# 1-Schematic_MOBO_V3.net
KiCad netlist of a schematic drawn in EasyEDA
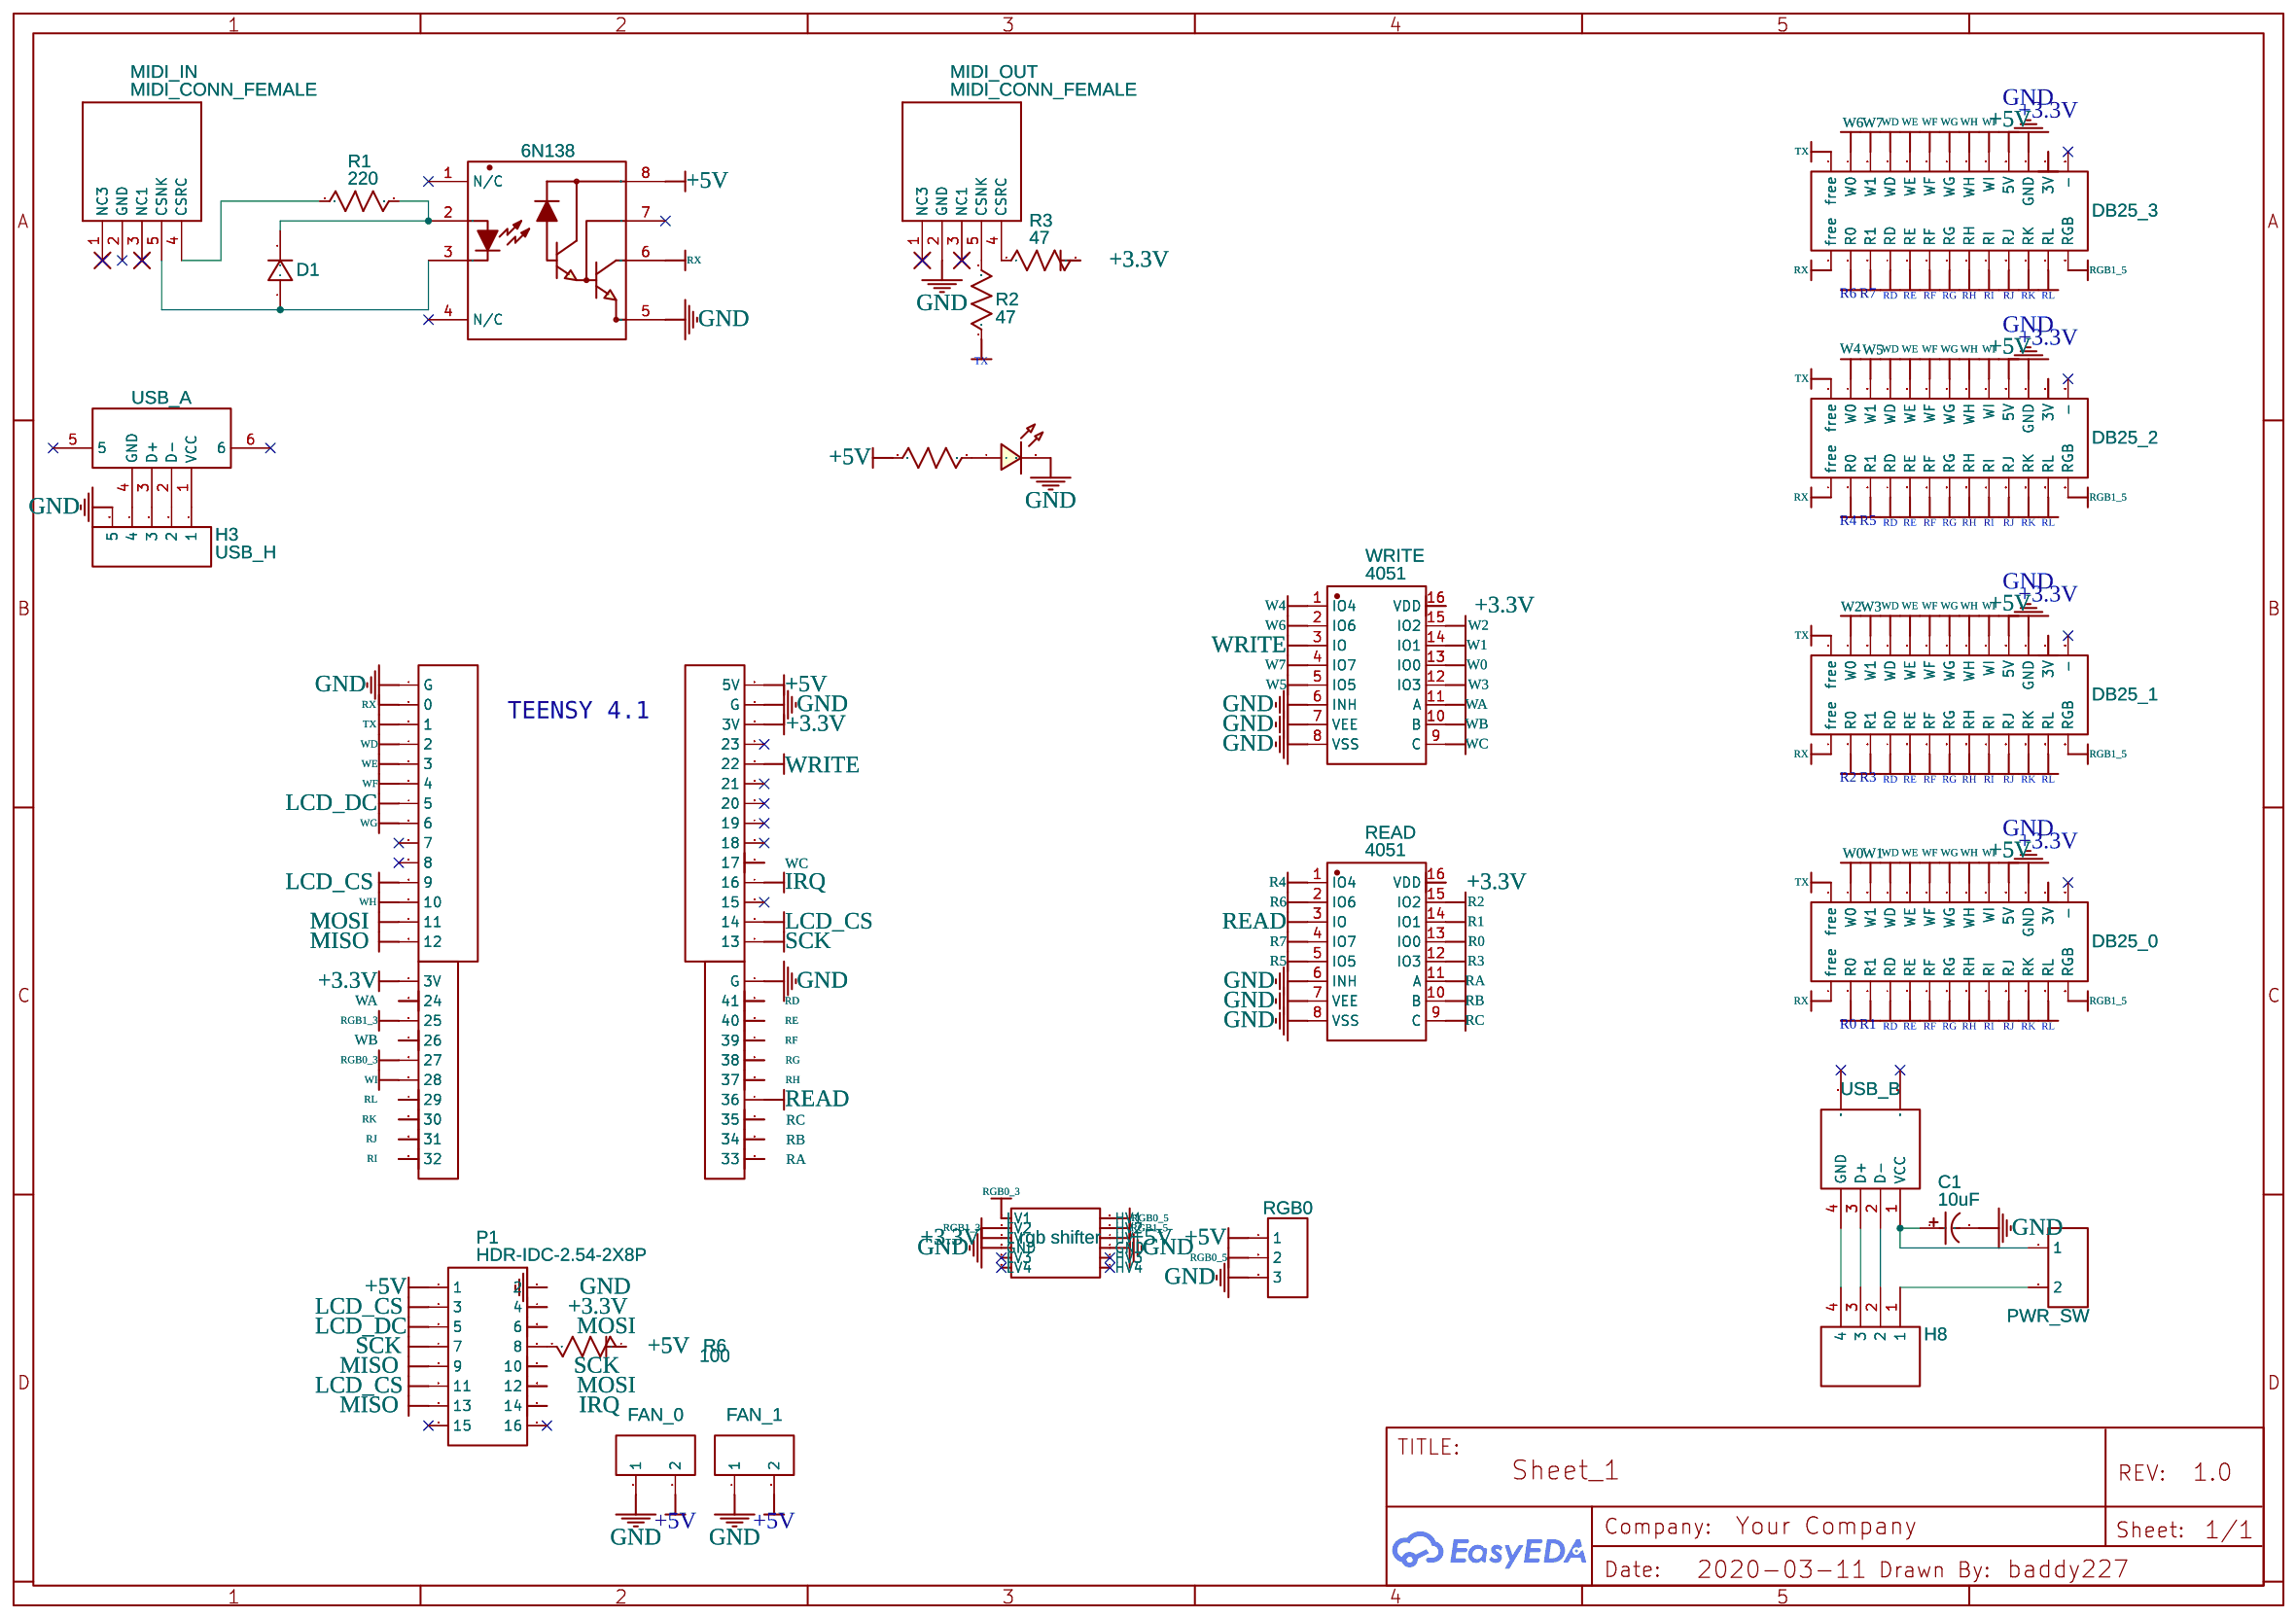
[diagram p0: schematic sheet]

(export (version "E")
  (design (tool "Eeschema 10.0.6"))
  (components
    (comp (ref "6N138")
      (value "6N138")
      (fields (field (name "BOM_Supplier Part") "C255743"))
      (libsource (lib "") (part "6N138"))
    )
    (comp (ref "C1")
      (value "10uF")
      (fields
        (field (name "BOM_Manufacturer Part") "C10uF63V2.5mm5x11mm")
        (field (name "BOM_Supplier Part") "C32455")
      )
      (libsource (lib "") (part "C10uF63V2.5mm5x11mm"))
    )
    (comp (ref "D1")
      (value "1N4448")
      (fields (field (name "BOM_Supplier Part") "C54037"))
      (libsource (lib "") (part "1N4448"))
    )
    (comp (ref "DB25_0")
      (value "HDR-IDC-2.54-2X13P")
      (fields (field (name "BOM_Manufacturer Part") "IDC Box 2.54mm 2X13P Straight"))
      (libsource (lib "") (part "HDR-IDC-2.54-2X13P"))
    )
    (comp (ref "DB25_1")
      (value "HDR-IDC-2.54-2X13P")
      (fields (field (name "BOM_Manufacturer Part") "IDC Box 2.54mm 2X13P Straight"))
      (libsource (lib "") (part "HDR-IDC-2.54-2X13P"))
    )
    (comp (ref "DB25_2")
      (value "HDR-IDC-2.54-2X13P")
      (fields (field (name "BOM_Manufacturer Part") "IDC Box 2.54mm 2X13P Straight"))
      (libsource (lib "") (part "HDR-IDC-2.54-2X13P"))
    )
    (comp (ref "DB25_3")
      (value "HDR-IDC-2.54-2X13P")
      (fields (field (name "BOM_Manufacturer Part") "IDC Box 2.54mm 2X13P Straight"))
      (libsource (lib "") (part "HDR-IDC-2.54-2X13P"))
    )
    (comp (ref "FAN_0")
      (value "Header-Male-2.54_1x2")
      (fields (field (name "BOM_Manufacturer Part") "826629-2") (field (name "BOM_Supplier Part") "C86471"))
      (libsource (lib "") (part "Header-Male-2.54_1x2"))
    )
    (comp (ref "FAN_1")
      (value "Header-Male-2.54_1x2")
      (fields (field (name "BOM_Manufacturer Part") "826629-2") (field (name "BOM_Supplier Part") "C86471"))
      (libsource (lib "") (part "Header-Male-2.54_1x2"))
    )
    (comp (ref "H1")
      (value "HDR-F-2.54_1x10")
      (fields (field (name "BOM_Supplier Part") "C35445"))
      (libsource (lib "") (part "HDR-F-2.54_1x10"))
    )
    (comp (ref "H2")
      (value "HDR-F-2.54_1x10")
      (fields (field (name "BOM_Supplier Part") "C35445"))
      (libsource (lib "") (part "HDR-F-2.54_1x10_1"))
    )
    (comp (ref "H3")
      (value "USB_H")
      (fields (field (name "BOM_Supplier Part") "C50950"))
      (libsource (lib "") (part "HDR-F-2.54_1x5"))
    )
    (comp (ref "H8")
      (value "220S-1*4P H=8.5MM Ytype Gold-plated")
      (fields (field (name "BOM_Supplier Part") "C124413"))
      (libsource (lib "") (part "220S-1*4P H=8.5MM Ytype Gold-plated"))
    )
    (comp (ref "LED1")
      (value "LED-TH-3mm_R")
      (fields
        (field (name "BOM_Manufacturer Part") "204-10SDRD/S530-A3-L")
        (field (name "BOM_Supplier Part") "C84774")
      )
      (libsource (lib "") (part "LED-TH-3mm_R"))
    )
    (comp (ref "MIDI_IN") (value "MIDI_CONN_FEMALE") (libsource (lib "") (part "MIDI_CONN_FEMALE")))
    (comp (ref "MIDI_OUT") (value "MIDI_CONN_FEMALE") (libsource (lib "") (part "MIDI_CONN_FEMALE_1")))
    (comp (ref "P1")
      (value "HDR-IDC-2.54-2X8P")
      (fields
        (field (name "BOM_Manufacturer Part") "IDC Box 2.54mm 16P　Straight")
        (field (name "BOM_Supplier Part") "C3406")
      )
      (libsource (lib "") (part "HDR-IDC-2.54-2X8P"))
    )
    (comp (ref "PWR_SW")
      (value "Header-Male-2.54_1x2")
      (fields (field (name "BOM_Manufacturer Part") "826629-2") (field (name "BOM_Supplier Part") "C86471"))
      (libsource (lib "") (part "Header-Male-2.54_1x2_1"))
    )
    (comp (ref "R1") (value "220") (libsource (lib "") (part "Res_AXIAL-0.3(1/8W)_US")))
    (comp (ref "R2") (value "47") (libsource (lib "") (part "Res_AXIAL-0.3(1/8W)_US_1")))
    (comp (ref "R3") (value "47") (libsource (lib "") (part "Res_AXIAL-0.3(1/8W)_US")))
    (comp (ref "R4") (value "1k") (libsource (lib "") (part "R_AXIAL-0.3_US_1")))
    (comp (ref "R6") (value "100") (libsource (lib "") (part "R_AXIAL-0.3_US")))
    (comp (ref "READ")
      (value "4051")
      (fields (field (name "BOM_Manufacturer Part") "CD4051BE") (field (name "BOM_Supplier Part") "C5200"))
      (libsource (lib "") (part "CD4051BE_1"))
    )
    (comp (ref "RGB0")
      (value "Header-Male-2.54_1x3")
      (fields
        (field (name "BOM_Manufacturer Part") "Header2.54mm 1*3P")
        (field (name "BOM_Supplier Part") "C49257")
      )
      (libsource (lib "") (part "Header-Male-2.54_1x3"))
    )
    (comp (ref "T0")
      (value "Female header 2.54-1*14P")
      (fields (field (name "BOM_Supplier Part") "C52711"))
      (libsource (lib "") (part "Female header 2.54-1*14P"))
    )
    (comp (ref "T1")
      (value "Female header 2.54-1*14P")
      (fields (field (name "BOM_Supplier Part") "C52711"))
      (libsource (lib "") (part "Female header 2.54-1*14P_1"))
    )
    (comp (ref "U1")
      (value "rgb shifter")
      (fields (field (name "BOM_Manufacturer Part") "4 channel logic level shifter bss138"))
      (libsource (lib "") (part "4 channel logic level shifter bss138"))
    )
    (comp (ref "USB_A")
      (value "USB-AF-90-13.6X14.4-H6.95")
      (fields (field (name "BOM_Supplier Part") "C42628"))
      (libsource (lib "") (part "USB-AF-90-13.6X14.4-H6.95"))
    )
    (comp (ref "USB_B")
      (value "USB-B-Female-TH_C46393")
      (fields
        (field (name "BOM_Manufacturer Part") "USB-B-Female-90-TH")
        (field (name "BOM_Supplier Part") "C46393")
      )
      (libsource (lib "") (part "USB-B-Female-TH_C46393"))
    )
    (comp (ref "WRITE")
      (value "4051")
      (fields (field (name "BOM_Manufacturer Part") "CD4051BE") (field (name "BOM_Supplier Part") "C5200"))
      (libsource (lib "") (part "CD4051BE"))
    )
  )
  (nets
    (net (code "1") (name "+3.3V") (class "Default")
      (node (ref "DB25_0") (pin "24") (pinfunction "3V_24") (pintype "unspecified"))
      (node (ref "DB25_1") (pin "24") (pinfunction "3V_24") (pintype "unspecified"))
      (node (ref "DB25_2") (pin "24") (pinfunction "3V_24") (pintype "unspecified"))
      (node (ref "DB25_3") (pin "24") (pinfunction "3V_24") (pintype "unspecified"))
      (node (ref "H1") (pin "1") (pinfunction "3V_1") (pintype "unspecified"))
      (node (ref "P1") (pin "4") (pinfunction "4_4") (pintype "unspecified"))
      (node (ref "R3") (pin "2") (pinfunction "2_2") (pintype "unspecified"))
      (node (ref "READ") (pin "16") (pinfunction "VDD_16") (pintype "unspecified"))
      (node (ref "T1") (pin "12") (pinfunction "3V_12") (pintype "input"))
      (node (ref "U1") (pin "9") (pinfunction "LV_9") (pintype "unspecified"))
      (node (ref "WRITE") (pin "16") (pinfunction "VDD_16") (pintype "unspecified"))
    )
    (net (code "2") (name "+5V") (class "Default")
      (node (ref "6N138") (pin "8") (pinfunction "VCC_8") (pintype "unspecified"))
      (node (ref "DB25_0") (pin "20") (pinfunction "5V_20") (pintype "unspecified"))
      (node (ref "DB25_1") (pin "20") (pinfunction "5V_20") (pintype "unspecified"))
      (node (ref "DB25_2") (pin "20") (pinfunction "5V_20") (pintype "unspecified"))
      (node (ref "DB25_3") (pin "20") (pinfunction "5V_20") (pintype "unspecified"))
      (node (ref "FAN_0") (pin "2") (pinfunction "2_2") (pintype "unspecified"))
      (node (ref "FAN_1") (pin "2") (pinfunction "2_2") (pintype "unspecified"))
      (node (ref "P1") (pin "1") (pinfunction "1_1") (pintype "unspecified"))
      (node (ref "R4") (pin "1") (pinfunction "1_1") (pintype "unspecified"))
      (node (ref "R6") (pin "1") (pinfunction "1_1") (pintype "unspecified"))
      (node (ref "RGB0") (pin "1") (pinfunction "1_1") (pintype "input"))
      (node (ref "T1") (pin "14") (pinfunction "5V_14") (pintype "input"))
      (node (ref "U1") (pin "4") (pinfunction "HV_4") (pintype "unspecified"))
    )
    (net (code "3") (name "GND") (class "Default")
      (node (ref "6N138") (pin "5") (pinfunction "GND_5") (pintype "unspecified"))
      (node (ref "C1") (pin "2") (pinfunction "2_2") (pintype "input"))
      (node (ref "DB25_0") (pin "22") (pinfunction "GND_22") (pintype "unspecified"))
      (node (ref "DB25_1") (pin "22") (pinfunction "GND_22") (pintype "unspecified"))
      (node (ref "DB25_2") (pin "22") (pinfunction "GND_22") (pintype "unspecified"))
      (node (ref "DB25_3") (pin "22") (pinfunction "GND_22") (pintype "unspecified"))
      (node (ref "FAN_0") (pin "1") (pinfunction "1_1") (pintype "unspecified"))
      (node (ref "FAN_1") (pin "1") (pinfunction "1_1") (pintype "unspecified"))
      (node (ref "H2") (pin "1") (pinfunction "G_1") (pintype "unspecified"))
      (node (ref "H3") (pin "5") (pinfunction "5_5") (pintype "unspecified"))
      (node (ref "LED1") (pin "2") (pinfunction "2_2") (pintype "unspecified"))
      (node (ref "MIDI_OUT") (pin "2") (pinfunction "GND_2") (pintype "unspecified"))
      (node (ref "P1") (pin "2") (pinfunction "2_2") (pintype "unspecified"))
      (node (ref "READ") (pin "6") (pinfunction "INH_6") (pintype "unspecified"))
      (node (ref "READ") (pin "7") (pinfunction "VEE_7") (pintype "unspecified"))
      (node (ref "READ") (pin "8") (pinfunction "VSS_8") (pintype "unspecified"))
      (node (ref "RGB0") (pin "3") (pinfunction "3_3") (pintype "input"))
      (node (ref "T0") (pin "1") (pinfunction "G_1") (pintype "input"))
      (node (ref "T1") (pin "13") (pinfunction "G_13") (pintype "input"))
      (node (ref "U1") (pin "10") (pinfunction "GND_10") (pintype "unspecified"))
      (node (ref "U1") (pin "3") (pinfunction "GND_3") (pintype "unspecified"))
      (node (ref "WRITE") (pin "6") (pinfunction "INH_6") (pintype "unspecified"))
      (node (ref "WRITE") (pin "7") (pinfunction "VEE_7") (pintype "unspecified"))
      (node (ref "WRITE") (pin "8") (pinfunction "VSS_8") (pintype "unspecified"))
    )
    (net (code "4") (name "IRQ") (class "Default")
      (node (ref "P1") (pin "14") (pinfunction "14_14") (pintype "unspecified"))
      (node (ref "T1") (pin "4") (pinfunction "16_4") (pintype "input"))
    )
    (net (code "5") (name "LCD_CS") (class "Default")
      (node (ref "P1") (pin "11") (pinfunction "11_11") (pintype "unspecified"))
      (node (ref "P1") (pin "3") (pinfunction "3_3") (pintype "unspecified"))
      (node (ref "T0") (pin "11") (pinfunction "9_11") (pintype "input"))
      (node (ref "T1") (pin "2") (pinfunction "14_2") (pintype "input"))
    )
    (net (code "6") (name "LCD_DC") (class "Default")
      (node (ref "P1") (pin "5") (pinfunction "5_5") (pintype "unspecified"))
      (node (ref "T0") (pin "7") (pinfunction "5_7") (pintype "input"))
    )
    (net (code "7") (name "MISO") (class "Default")
      (node (ref "P1") (pin "13") (pinfunction "13_13") (pintype "unspecified"))
      (node (ref "P1") (pin "9") (pinfunction "9_9") (pintype "unspecified"))
      (node (ref "T0") (pin "14") (pinfunction "12_14") (pintype "input"))
    )
    (net (code "8") (name "MOSI") (class "Default")
      (node (ref "P1") (pin "12") (pinfunction "12_12") (pintype "unspecified"))
      (node (ref "P1") (pin "6") (pinfunction "6_6") (pintype "unspecified"))
      (node (ref "T0") (pin "13") (pinfunction "11_13") (pintype "input"))
    )
    (net (code "9") (name "Net-(6N138-A)") (class "Default")
      (node (ref "6N138") (pin "2") (pinfunction "A_2") (pintype "unspecified"))
      (node (ref "D1") (pin "2") (pinfunction "K_2") (pintype "unspecified"))
      (node (ref "R1") (pin "2") (pinfunction "2_2") (pintype "unspecified"))
    )
    (net (code "10") (name "Net-(6N138-C)") (class "Default")
      (node (ref "6N138") (pin "3") (pinfunction "C_3") (pintype "unspecified"))
      (node (ref "D1") (pin "1") (pinfunction "A_1") (pintype "unspecified"))
      (node (ref "MIDI_IN") (pin "5") (pinfunction "CSNK_5") (pintype "unspecified"))
    )
    (net (code "11") (name "Net-(H8-Pad1)") (class "Default")
      (node (ref "H8") (pin "1") (pinfunction "1_1") (pintype "unspecified"))
      (node (ref "PWR_SW") (pin "2") (pinfunction "2_2") (pintype "unspecified"))
    )
    (net (code "12") (name "Net-(LED1-Pad1)") (class "Default")
      (node (ref "LED1") (pin "1") (pinfunction "1_1") (pintype "unspecified"))
      (node (ref "R4") (pin "2") (pinfunction "2_2") (pintype "unspecified"))
    )
    (net (code "13") (name "Net-(MIDI_IN-CSRC)") (class "Default")
      (node (ref "MIDI_IN") (pin "4") (pinfunction "CSRC_4") (pintype "unspecified"))
      (node (ref "R1") (pin "1") (pinfunction "1_1") (pintype "unspecified"))
    )
    (net (code "14") (name "Net-(MIDI_OUT-CSNK)") (class "Default")
      (node (ref "MIDI_OUT") (pin "5") (pinfunction "CSNK_5") (pintype "unspecified"))
      (node (ref "R2") (pin "2") (pinfunction "2_2") (pintype "unspecified"))
    )
    (net (code "15") (name "Net-(MIDI_OUT-CSRC)") (class "Default")
      (node (ref "MIDI_OUT") (pin "4") (pinfunction "CSRC_4") (pintype "unspecified"))
      (node (ref "R3") (pin "1") (pinfunction "1_1") (pintype "unspecified"))
    )
    (net (code "16") (name "Net-(P1-Pad8)") (class "Default")
      (node (ref "P1") (pin "8") (pinfunction "8_8") (pintype "unspecified"))
      (node (ref "R6") (pin "2") (pinfunction "2_2") (pintype "unspecified"))
    )
    (net (code "17") (name "Net-(USB_A-D+)") (class "Default")
      (node (ref "H3") (pin "3") (pinfunction "3_3") (pintype "unspecified"))
      (node (ref "USB_A") (pin "3") (pinfunction "D+_3") (pintype "unspecified"))
    )
    (net (code "18") (name "Net-(USB_A-D-)") (class "Default")
      (node (ref "H3") (pin "2") (pinfunction "2_2") (pintype "unspecified"))
      (node (ref "USB_A") (pin "2") (pinfunction "D-_2") (pintype "unspecified"))
    )
    (net (code "19") (name "Net-(USB_A-GND)") (class "Default")
      (node (ref "H3") (pin "4") (pinfunction "4_4") (pintype "unspecified"))
      (node (ref "USB_A") (pin "4") (pinfunction "GND_4") (pintype "unspecified"))
    )
    (net (code "20") (name "Net-(USB_A-VCC)") (class "Default")
      (node (ref "H3") (pin "1") (pinfunction "1_1") (pintype "unspecified"))
      (node (ref "USB_A") (pin "1") (pinfunction "VCC_1") (pintype "unspecified"))
    )
    (net (code "21") (name "Net-(USB_B-D+)") (class "Default")
      (node (ref "H8") (pin "3") (pinfunction "3_3") (pintype "unspecified"))
      (node (ref "USB_B") (pin "3") (pinfunction "D+_3") (pintype "input"))
    )
    (net (code "22") (name "Net-(USB_B-D-)") (class "Default")
      (node (ref "H8") (pin "2") (pinfunction "2_2") (pintype "unspecified"))
      (node (ref "USB_B") (pin "2") (pinfunction "D-_2") (pintype "input"))
    )
    (net (code "23") (name "Net-(USB_B-GND)") (class "Default")
      (node (ref "H8") (pin "4") (pinfunction "4_4") (pintype "unspecified"))
      (node (ref "USB_B") (pin "4") (pinfunction "GND_4") (pintype "input"))
    )
    (net (code "24") (name "Net-(USB_B-VCC)") (class "Default")
      (node (ref "C1") (pin "1") (pinfunction "1_1") (pintype "input"))
      (node (ref "PWR_SW") (pin "1") (pinfunction "1_1") (pintype "unspecified"))
      (node (ref "USB_B") (pin "1") (pinfunction "VCC_1") (pintype "input"))
    )
    (net (code "25") (name "R0") (class "Default")
      (node (ref "DB25_0") (pin "3") (pinfunction "R0_3") (pintype "unspecified"))
      (node (ref "READ") (pin "13") (pinfunction "IO0_13") (pintype "unspecified"))
    )
    (net (code "26") (name "R1") (class "Default")
      (node (ref "DB25_0") (pin "5") (pinfunction "R1_5") (pintype "unspecified"))
      (node (ref "READ") (pin "14") (pinfunction "IO1_14") (pintype "unspecified"))
    )
    (net (code "27") (name "R2") (class "Default")
      (node (ref "DB25_1") (pin "3") (pinfunction "R0_3") (pintype "unspecified"))
      (node (ref "READ") (pin "15") (pinfunction "IO2_15") (pintype "unspecified"))
    )
    (net (code "28") (name "R3") (class "Default")
      (node (ref "DB25_1") (pin "5") (pinfunction "R1_5") (pintype "unspecified"))
      (node (ref "READ") (pin "12") (pinfunction "IO3_12") (pintype "unspecified"))
    )
    (net (code "29") (name "R4") (class "Default")
      (node (ref "DB25_2") (pin "3") (pinfunction "R0_3") (pintype "unspecified"))
      (node (ref "READ") (pin "1") (pinfunction "IO4_1") (pintype "unspecified"))
    )
    (net (code "30") (name "R5") (class "Default")
      (node (ref "DB25_2") (pin "5") (pinfunction "R1_5") (pintype "unspecified"))
      (node (ref "READ") (pin "5") (pinfunction "IO5_5") (pintype "unspecified"))
    )
    (net (code "31") (name "R6") (class "Default")
      (node (ref "DB25_3") (pin "3") (pinfunction "R0_3") (pintype "unspecified"))
      (node (ref "READ") (pin "2") (pinfunction "IO6_2") (pintype "unspecified"))
    )
    (net (code "32") (name "R7") (class "Default")
      (node (ref "DB25_3") (pin "5") (pinfunction "R1_5") (pintype "unspecified"))
      (node (ref "READ") (pin "4") (pinfunction "IO7_4") (pintype "unspecified"))
    )
    (net (code "33") (name "RA") (class "Default")
      (node (ref "H2") (pin "10") (pinfunction "33_10") (pintype "unspecified"))
      (node (ref "READ") (pin "11") (pinfunction "A_11") (pintype "unspecified"))
    )
    (net (code "34") (name "RB") (class "Default")
      (node (ref "H2") (pin "9") (pinfunction "34_9") (pintype "unspecified"))
      (node (ref "READ") (pin "10") (pinfunction "B_10") (pintype "unspecified"))
    )
    (net (code "35") (name "RC") (class "Default")
      (node (ref "H2") (pin "8") (pinfunction "35_8") (pintype "unspecified"))
      (node (ref "READ") (pin "9") (pinfunction "C_9") (pintype "unspecified"))
    )
    (net (code "36") (name "RD") (class "Default")
      (node (ref "DB25_0") (pin "7") (pinfunction "RD_7") (pintype "unspecified"))
      (node (ref "DB25_1") (pin "7") (pinfunction "RD_7") (pintype "unspecified"))
      (node (ref "DB25_2") (pin "7") (pinfunction "RD_7") (pintype "unspecified"))
      (node (ref "DB25_3") (pin "7") (pinfunction "RD_7") (pintype "unspecified"))
      (node (ref "H2") (pin "2") (pinfunction "41_2") (pintype "unspecified"))
    )
    (net (code "37") (name "RE") (class "Default")
      (node (ref "DB25_0") (pin "9") (pinfunction "RE_9") (pintype "unspecified"))
      (node (ref "DB25_1") (pin "9") (pinfunction "RE_9") (pintype "unspecified"))
      (node (ref "DB25_2") (pin "9") (pinfunction "RE_9") (pintype "unspecified"))
      (node (ref "DB25_3") (pin "9") (pinfunction "RE_9") (pintype "unspecified"))
      (node (ref "H2") (pin "3") (pinfunction "40_3") (pintype "unspecified"))
    )
    (net (code "38") (name "READ") (class "Default")
      (node (ref "H2") (pin "7") (pinfunction "36_7") (pintype "unspecified"))
      (node (ref "READ") (pin "3") (pinfunction "IO_3") (pintype "unspecified"))
    )
    (net (code "39") (name "RF") (class "Default")
      (node (ref "DB25_0") (pin "11") (pinfunction "RF_11") (pintype "unspecified"))
      (node (ref "DB25_1") (pin "11") (pinfunction "RF_11") (pintype "unspecified"))
      (node (ref "DB25_2") (pin "11") (pinfunction "RF_11") (pintype "unspecified"))
      (node (ref "DB25_3") (pin "11") (pinfunction "RF_11") (pintype "unspecified"))
      (node (ref "H2") (pin "4") (pinfunction "39_4") (pintype "unspecified"))
    )
    (net (code "40") (name "RG") (class "Default")
      (node (ref "DB25_0") (pin "13") (pinfunction "RG_13") (pintype "unspecified"))
      (node (ref "DB25_1") (pin "13") (pinfunction "RG_13") (pintype "unspecified"))
      (node (ref "DB25_2") (pin "13") (pinfunction "RG_13") (pintype "unspecified"))
      (node (ref "DB25_3") (pin "13") (pinfunction "RG_13") (pintype "unspecified"))
      (node (ref "H2") (pin "5") (pinfunction "38_5") (pintype "unspecified"))
    )
    (net (code "41") (name "RGB0_3") (class "Default")
      (node (ref "H1") (pin "5") (pinfunction "27_5") (pintype "unspecified"))
      (node (ref "U1") (pin "7") (pinfunction "LV1_7") (pintype "unspecified"))
    )
    (net (code "42") (name "RGB0_5") (class "Default")
      (node (ref "RGB0") (pin "2") (pinfunction "2_2") (pintype "input"))
      (node (ref "U1") (pin "6") (pinfunction "HV1_6") (pintype "unspecified"))
    )
    (net (code "43") (name "RGB1_3") (class "Default")
      (node (ref "H1") (pin "3") (pinfunction "25_3") (pintype "unspecified"))
      (node (ref "U1") (pin "8") (pinfunction "LV2_8") (pintype "unspecified"))
    )
    (net (code "44") (name "RGB1_5") (class "Default")
      (node (ref "DB25_0") (pin "25") (pinfunction "RGB_25") (pintype "unspecified"))
      (node (ref "DB25_1") (pin "25") (pinfunction "RGB_25") (pintype "unspecified"))
      (node (ref "DB25_2") (pin "25") (pinfunction "RGB_25") (pintype "unspecified"))
      (node (ref "DB25_3") (pin "25") (pinfunction "RGB_25") (pintype "unspecified"))
      (node (ref "U1") (pin "5") (pinfunction "HV2_5") (pintype "unspecified"))
    )
    (net (code "45") (name "RH") (class "Default")
      (node (ref "DB25_0") (pin "15") (pinfunction "RH_15") (pintype "unspecified"))
      (node (ref "DB25_1") (pin "15") (pinfunction "RH_15") (pintype "unspecified"))
      (node (ref "DB25_2") (pin "15") (pinfunction "RH_15") (pintype "unspecified"))
      (node (ref "DB25_3") (pin "15") (pinfunction "RH_15") (pintype "unspecified"))
      (node (ref "H2") (pin "6") (pinfunction "37_6") (pintype "unspecified"))
    )
    (net (code "46") (name "RI") (class "Default")
      (node (ref "DB25_0") (pin "17") (pinfunction "RI_17") (pintype "unspecified"))
      (node (ref "DB25_1") (pin "17") (pinfunction "RI_17") (pintype "unspecified"))
      (node (ref "DB25_2") (pin "17") (pinfunction "RI_17") (pintype "unspecified"))
      (node (ref "DB25_3") (pin "17") (pinfunction "RI_17") (pintype "unspecified"))
      (node (ref "H1") (pin "10") (pinfunction "32_10") (pintype "unspecified"))
    )
    (net (code "47") (name "RJ") (class "Default")
      (node (ref "DB25_0") (pin "19") (pinfunction "RJ_19") (pintype "unspecified"))
      (node (ref "DB25_1") (pin "19") (pinfunction "RJ_19") (pintype "unspecified"))
      (node (ref "DB25_2") (pin "19") (pinfunction "RJ_19") (pintype "unspecified"))
      (node (ref "DB25_3") (pin "19") (pinfunction "RJ_19") (pintype "unspecified"))
      (node (ref "H1") (pin "9") (pinfunction "31_9") (pintype "unspecified"))
    )
    (net (code "48") (name "RK") (class "Default")
      (node (ref "DB25_0") (pin "21") (pinfunction "RK_21") (pintype "unspecified"))
      (node (ref "DB25_1") (pin "21") (pinfunction "RK_21") (pintype "unspecified"))
      (node (ref "DB25_2") (pin "21") (pinfunction "RK_21") (pintype "unspecified"))
      (node (ref "DB25_3") (pin "21") (pinfunction "RK_21") (pintype "unspecified"))
      (node (ref "H1") (pin "8") (pinfunction "30_8") (pintype "unspecified"))
    )
    (net (code "49") (name "RL") (class "Default")
      (node (ref "DB25_0") (pin "23") (pinfunction "RL_23") (pintype "unspecified"))
      (node (ref "DB25_1") (pin "23") (pinfunction "RL_23") (pintype "unspecified"))
      (node (ref "DB25_2") (pin "23") (pinfunction "RL_23") (pintype "unspecified"))
      (node (ref "DB25_3") (pin "23") (pinfunction "RL_23") (pintype "unspecified"))
      (node (ref "H1") (pin "7") (pinfunction "29_7") (pintype "unspecified"))
    )
    (net (code "50") (name "RX") (class "Default")
      (node (ref "6N138") (pin "6") (pinfunction "VOUT_6") (pintype "unspecified"))
      (node (ref "DB25_0") (pin "1") (pinfunction "free_1") (pintype "unspecified"))
      (node (ref "DB25_1") (pin "1") (pinfunction "free_1") (pintype "unspecified"))
      (node (ref "DB25_2") (pin "1") (pinfunction "free_1") (pintype "unspecified"))
      (node (ref "DB25_3") (pin "1") (pinfunction "free_1") (pintype "unspecified"))
      (node (ref "T0") (pin "2") (pinfunction "0_2") (pintype "input"))
    )
    (net (code "51") (name "SCK") (class "Default")
      (node (ref "P1") (pin "10") (pinfunction "10_10") (pintype "unspecified"))
      (node (ref "P1") (pin "7") (pinfunction "7_7") (pintype "unspecified"))
      (node (ref "T1") (pin "1") (pinfunction "13_1") (pintype "input"))
    )
    (net (code "52") (name "TX") (class "Default")
      (node (ref "DB25_0") (pin "2") (pinfunction "free_2") (pintype "unspecified"))
      (node (ref "DB25_1") (pin "2") (pinfunction "free_2") (pintype "unspecified"))
      (node (ref "DB25_2") (pin "2") (pinfunction "free_2") (pintype "unspecified"))
      (node (ref "DB25_3") (pin "2") (pinfunction "free_2") (pintype "unspecified"))
      (node (ref "R2") (pin "1") (pinfunction "1_1") (pintype "unspecified"))
      (node (ref "T0") (pin "3") (pinfunction "1_3") (pintype "input"))
    )
    (net (code "53") (name "W0") (class "Default")
      (node (ref "DB25_0") (pin "4") (pinfunction "W0_4") (pintype "unspecified"))
      (node (ref "WRITE") (pin "13") (pinfunction "IO0_13") (pintype "unspecified"))
    )
    (net (code "54") (name "W1") (class "Default")
      (node (ref "DB25_0") (pin "6") (pinfunction "W1_6") (pintype "unspecified"))
      (node (ref "WRITE") (pin "14") (pinfunction "IO1_14") (pintype "unspecified"))
    )
    (net (code "55") (name "W2") (class "Default")
      (node (ref "DB25_1") (pin "4") (pinfunction "W0_4") (pintype "unspecified"))
      (node (ref "WRITE") (pin "15") (pinfunction "IO2_15") (pintype "unspecified"))
    )
    (net (code "56") (name "W3") (class "Default")
      (node (ref "DB25_1") (pin "6") (pinfunction "W1_6") (pintype "unspecified"))
      (node (ref "WRITE") (pin "12") (pinfunction "IO3_12") (pintype "unspecified"))
    )
    (net (code "57") (name "W4") (class "Default")
      (node (ref "DB25_2") (pin "4") (pinfunction "W0_4") (pintype "unspecified"))
      (node (ref "WRITE") (pin "1") (pinfunction "IO4_1") (pintype "unspecified"))
    )
    (net (code "58") (name "W5") (class "Default")
      (node (ref "DB25_2") (pin "6") (pinfunction "W1_6") (pintype "unspecified"))
      (node (ref "WRITE") (pin "5") (pinfunction "IO5_5") (pintype "unspecified"))
    )
    (net (code "59") (name "W6") (class "Default")
      (node (ref "DB25_3") (pin "4") (pinfunction "W0_4") (pintype "unspecified"))
      (node (ref "WRITE") (pin "2") (pinfunction "IO6_2") (pintype "unspecified"))
    )
    (net (code "60") (name "W7") (class "Default")
      (node (ref "DB25_3") (pin "6") (pinfunction "W1_6") (pintype "unspecified"))
      (node (ref "WRITE") (pin "4") (pinfunction "IO7_4") (pintype "unspecified"))
    )
    (net (code "61") (name "WA") (class "Default")
      (node (ref "H1") (pin "2") (pinfunction "24_2") (pintype "unspecified"))
      (node (ref "WRITE") (pin "11") (pinfunction "A_11") (pintype "unspecified"))
    )
    (net (code "62") (name "WB") (class "Default")
      (node (ref "H1") (pin "4") (pinfunction "26_4") (pintype "unspecified"))
      (node (ref "WRITE") (pin "10") (pinfunction "B_10") (pintype "unspecified"))
    )
    (net (code "63") (name "WC") (class "Default")
      (node (ref "T1") (pin "5") (pinfunction "17_5") (pintype "input"))
      (node (ref "WRITE") (pin "9") (pinfunction "C_9") (pintype "unspecified"))
    )
    (net (code "64") (name "WD") (class "Default")
      (node (ref "DB25_0") (pin "8") (pinfunction "WD_8") (pintype "unspecified"))
      (node (ref "DB25_1") (pin "8") (pinfunction "WD_8") (pintype "unspecified"))
      (node (ref "DB25_2") (pin "8") (pinfunction "WD_8") (pintype "unspecified"))
      (node (ref "DB25_3") (pin "8") (pinfunction "WD_8") (pintype "unspecified"))
      (node (ref "T0") (pin "4") (pinfunction "2_4") (pintype "input"))
    )
    (net (code "65") (name "WE") (class "Default")
      (node (ref "DB25_0") (pin "10") (pinfunction "WE_10") (pintype "unspecified"))
      (node (ref "DB25_1") (pin "10") (pinfunction "WE_10") (pintype "unspecified"))
      (node (ref "DB25_2") (pin "10") (pinfunction "WE_10") (pintype "unspecified"))
      (node (ref "DB25_3") (pin "10") (pinfunction "WE_10") (pintype "unspecified"))
      (node (ref "T0") (pin "5") (pinfunction "3_5") (pintype "input"))
    )
    (net (code "66") (name "WF") (class "Default")
      (node (ref "DB25_0") (pin "12") (pinfunction "WF_12") (pintype "unspecified"))
      (node (ref "DB25_1") (pin "12") (pinfunction "WF_12") (pintype "unspecified"))
      (node (ref "DB25_2") (pin "12") (pinfunction "WF_12") (pintype "unspecified"))
      (node (ref "DB25_3") (pin "12") (pinfunction "WF_12") (pintype "unspecified"))
      (node (ref "T0") (pin "6") (pinfunction "4_6") (pintype "input"))
    )
    (net (code "67") (name "WG") (class "Default")
      (node (ref "DB25_0") (pin "14") (pinfunction "WG_14") (pintype "unspecified"))
      (node (ref "DB25_1") (pin "14") (pinfunction "WG_14") (pintype "unspecified"))
      (node (ref "DB25_2") (pin "14") (pinfunction "WG_14") (pintype "unspecified"))
      (node (ref "DB25_3") (pin "14") (pinfunction "WG_14") (pintype "unspecified"))
      (node (ref "T0") (pin "8") (pinfunction "6_8") (pintype "input"))
    )
    (net (code "68") (name "WH") (class "Default")
      (node (ref "DB25_0") (pin "16") (pinfunction "WH_16") (pintype "unspecified"))
      (node (ref "DB25_1") (pin "16") (pinfunction "WH_16") (pintype "unspecified"))
      (node (ref "DB25_2") (pin "16") (pinfunction "WH_16") (pintype "unspecified"))
      (node (ref "DB25_3") (pin "16") (pinfunction "WH_16") (pintype "unspecified"))
      (node (ref "T0") (pin "12") (pinfunction "10_12") (pintype "input"))
    )
    (net (code "69") (name "WI") (class "Default")
      (node (ref "DB25_0") (pin "18") (pinfunction "WI_18") (pintype "unspecified"))
      (node (ref "DB25_1") (pin "18") (pinfunction "WI_18") (pintype "unspecified"))
      (node (ref "DB25_2") (pin "18") (pinfunction "WI_18") (pintype "unspecified"))
      (node (ref "DB25_3") (pin "18") (pinfunction "WI_18") (pintype "unspecified"))
      (node (ref "H1") (pin "6") (pinfunction "28_6") (pintype "unspecified"))
    )
    (net (code "70") (name "WRITE") (class "Default")
      (node (ref "T1") (pin "10") (pinfunction "22_10") (pintype "input"))
      (node (ref "WRITE") (pin "3") (pinfunction "IO_3") (pintype "unspecified"))
    )
    (net (code "71") (name "unconnected-(6N138-N{slash}C-Pad1)") (class "Default")
      (node (ref "6N138") (pin "1") (pinfunction "N/C_1") (pintype "unspecified+no_connect"))
    )
    (net (code "72") (name "unconnected-(6N138-N{slash}C-Pad4)") (class "Default")
      (node (ref "6N138") (pin "4") (pinfunction "N/C_4") (pintype "unspecified+no_connect"))
    )
    (net (code "73") (name "unconnected-(6N138-VB-Pad7)") (class "Default")
      (node (ref "6N138") (pin "7") (pinfunction "VB_7") (pintype "unspecified+no_connect"))
    )
    (net (code "74") (name "unconnected-(DB25_0---Pad26)") (class "Default")
      (node (ref "DB25_0") (pin "26") (pinfunction "-_26") (pintype "unspecified+no_connect"))
    )
    (net (code "75") (name "unconnected-(DB25_1---Pad26)") (class "Default")
      (node (ref "DB25_1") (pin "26") (pinfunction "-_26") (pintype "unspecified+no_connect"))
    )
    (net (code "76") (name "unconnected-(DB25_2---Pad26)") (class "Default")
      (node (ref "DB25_2") (pin "26") (pinfunction "-_26") (pintype "unspecified+no_connect"))
    )
    (net (code "77") (name "unconnected-(DB25_3---Pad26)") (class "Default")
      (node (ref "DB25_3") (pin "26") (pinfunction "-_26") (pintype "unspecified+no_connect"))
    )
    (net (code "78") (name "unconnected-(MIDI_IN-GND-Pad2)") (class "Default")
      (node (ref "MIDI_IN") (pin "2") (pinfunction "GND_2") (pintype "unspecified+no_connect"))
    )
    (net (code "79") (name "unconnected-(MIDI_IN-NC1-Pad3)") (class "Default")
      (node (ref "MIDI_IN") (pin "3") (pinfunction "NC1_3") (pintype "unspecified+no_connect"))
    )
    (net (code "80") (name "unconnected-(MIDI_IN-NC3-Pad1)") (class "Default")
      (node (ref "MIDI_IN") (pin "1") (pinfunction "NC3_1") (pintype "unspecified+no_connect"))
    )
    (net (code "81") (name "unconnected-(MIDI_OUT-NC1-Pad3)") (class "Default")
      (node (ref "MIDI_OUT") (pin "3") (pinfunction "NC1_3") (pintype "unspecified+no_connect"))
    )
    (net (code "82") (name "unconnected-(MIDI_OUT-NC3-Pad1)") (class "Default")
      (node (ref "MIDI_OUT") (pin "1") (pinfunction "NC3_1") (pintype "unspecified+no_connect"))
    )
    (net (code "83") (name "unconnected-(P1-Pad15)") (class "Default")
      (node (ref "P1") (pin "15") (pinfunction "15_15") (pintype "unspecified+no_connect"))
    )
    (net (code "84") (name "unconnected-(P1-Pad16)") (class "Default")
      (node (ref "P1") (pin "16") (pinfunction "16_16") (pintype "unspecified+no_connect"))
    )
    (net (code "85") (name "unconnected-(T0-7-Pad9)") (class "Default")
      (node (ref "T0") (pin "9") (pinfunction "7_9") (pintype "input+no_connect"))
    )
    (net (code "86") (name "unconnected-(T0-8-Pad10)") (class "Default")
      (node (ref "T0") (pin "10") (pinfunction "8_10") (pintype "input+no_connect"))
    )
    (net (code "87") (name "unconnected-(T1-15-Pad3)") (class "Default")
      (node (ref "T1") (pin "3") (pinfunction "15_3") (pintype "input+no_connect"))
    )
    (net (code "88") (name "unconnected-(T1-18-Pad6)") (class "Default")
      (node (ref "T1") (pin "6") (pinfunction "18_6") (pintype "input+no_connect"))
    )
    (net (code "89") (name "unconnected-(T1-19-Pad7)") (class "Default")
      (node (ref "T1") (pin "7") (pinfunction "19_7") (pintype "input+no_connect"))
    )
    (net (code "90") (name "unconnected-(T1-20-Pad8)") (class "Default")
      (node (ref "T1") (pin "8") (pinfunction "20_8") (pintype "input+no_connect"))
    )
    (net (code "91") (name "unconnected-(T1-21-Pad9)") (class "Default")
      (node (ref "T1") (pin "9") (pinfunction "21_9") (pintype "input+no_connect"))
    )
    (net (code "92") (name "unconnected-(T1-23-Pad11)") (class "Default")
      (node (ref "T1") (pin "11") (pinfunction "23_11") (pintype "input+no_connect"))
    )
    (net (code "93") (name "unconnected-(U1-HV3-Pad2)") (class "Default")
      (node (ref "U1") (pin "2") (pinfunction "HV3_2") (pintype "unspecified+no_connect"))
    )
    (net (code "94") (name "unconnected-(U1-HV4-Pad1)") (class "Default")
      (node (ref "U1") (pin "1") (pinfunction "HV4_1") (pintype "unspecified+no_connect"))
    )
    (net (code "95") (name "unconnected-(U1-LV3-Pad11)") (class "Default")
      (node (ref "U1") (pin "11") (pinfunction "LV3_11") (pintype "unspecified+no_connect"))
    )
    (net (code "96") (name "unconnected-(U1-LV4-Pad12)") (class "Default")
      (node (ref "U1") (pin "12") (pinfunction "LV4_12") (pintype "unspecified+no_connect"))
    )
    (net (code "97") (name "unconnected-(USB_A-Pad5)") (class "Default")
      (node (ref "USB_A") (pin "5") (pinfunction "5_5") (pintype "unspecified+no_connect"))
    )
    (net (code "98") (name "unconnected-(USB_A-Pad6)") (class "Default")
      (node (ref "USB_A") (pin "6") (pinfunction "6_6") (pintype "unspecified+no_connect"))
    )
    (net (code "99") (name "unconnected-(USB_B-PadSH1)") (class "Default")
      (node (ref "USB_B") (pin "SH1") (pinfunction "SH1_SH1") (pintype "unspecified+no_connect"))
    )
    (net (code "100") (name "unconnected-(USB_B-PadSH2)") (class "Default")
      (node (ref "USB_B") (pin "SH2") (pinfunction "SH2_SH2") (pintype "unspecified+no_connect"))
    )
  )
)
